# Power_Supply_and_Buttons.net
KiCad netlist of a schematic drawn in Altium Designer
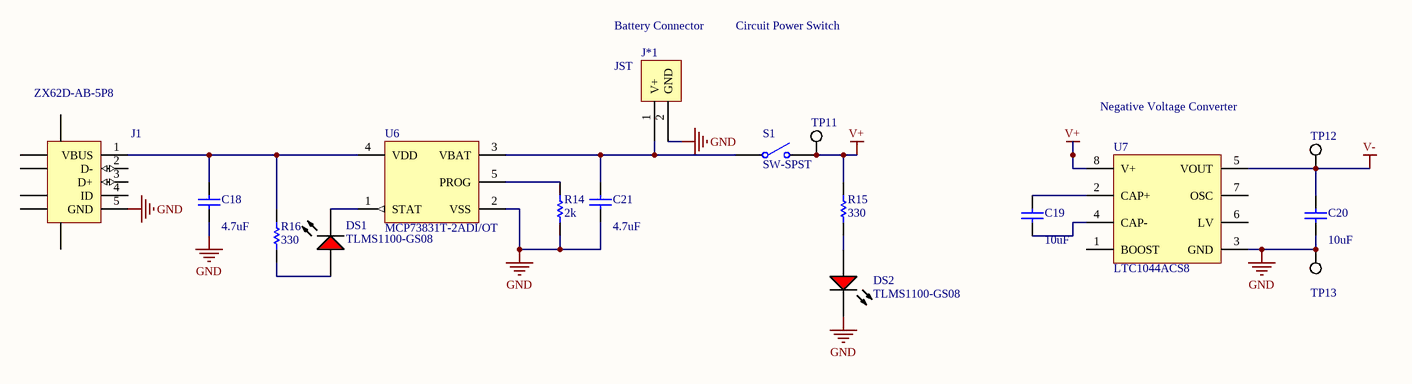
[diagram p0: Power_Supply_and_Buttons.SchDoc]

(export (version "E")
  (design (tool "Eeschema 10.0.6"))
  (components
    (comp (ref "C18")
      (value "4.7uF")
      (footprint "1608[0603]")
      (description "Capacitor (Semiconductor SIM Model)")
      (fields (field (name "PUBLISHER") "Altium Limited"))
      (libsource (lib "Miscellaneous Devices") (part "Cap Semi"))
    )
    (comp (ref "C19")
      (value "10uF")
      (footprint "1608[0603]")
      (description "Capacitor (Semiconductor SIM Model)")
      (fields (field (name "PUBLISHER") "Altium Limited"))
      (libsource (lib "Miscellaneous Devices") (part "Cap Semi"))
    )
    (comp (ref "C20")
      (value "10uF")
      (footprint "1608[0603]")
      (description "Capacitor (Semiconductor SIM Model)")
      (fields (field (name "PUBLISHER") "Altium Limited"))
      (libsource (lib "Miscellaneous Devices") (part "Cap Semi"))
    )
    (comp (ref "C21")
      (value "4.7uF")
      (footprint "1608[0603]")
      (description "Capacitor (Semiconductor SIM Model)")
      (fields (field (name "PUBLISHER") "Altium Limited"))
      (libsource (lib "Miscellaneous Devices") (part "Cap Semi"))
    )
    (comp (ref "DS1")
      (value "TLMS1100-GS08")
      (footprint "VISH-TLMX1100_V")
      (description "LED, RED, 2.1 V, -40 to 100 degC, 2-Pin SMD (0603), RoHS, Tape and Reel")
      (fields (field (name "TOLERANCE") "5%"))
      (libsource (lib "Altium Content Vault") (part "LED-RED-AK-2"))
    )
    (comp (ref "DS2")
      (value "TLMS1100-GS08")
      (footprint "VISH-TLMX1100_V")
      (description "LED, RED, 2.1 V, -40 to 100 degC, 2-Pin SMD (0603), RoHS, Tape and Reel")
      (fields (field (name "TOLERANCE") "5%"))
      (libsource (lib "Altium Content Vault") (part "LED-RED-AK-2"))
    )
    (comp (ref "J*1")
      (value "JST")
      (footprint "JST- S2B-PH-SM4-TB(LF)(SN)-2_V")
      (libsource (lib "JST- S2B-PH-SM4-TB(LF)(SN)-2_V") (part "JST"))
    )
    (comp (ref "J1")
      (value "ZX62D-AB-5P8")
      (footprint "HIRO-ZX62D-AB-5P8_V")
      (fields (field (name "MANUFACTURER") "Hirose Electric"))
      (libsource (lib "Altium Content Vault") (part "HIRO-ZX62D-AB-5P8-5"))
    )
    (comp (ref "R14")
      (value "2k")
      (footprint "6-0805_M")
      (description "Resistor")
      (fields (field (name "PUBLISHER") "Altium Limited"))
      (libsource (lib "Miscellaneous Devices") (part "Res1"))
    )
    (comp (ref "R15")
      (value "330")
      (footprint "6-0805_M")
      (description "Resistor")
      (fields (field (name "PUBLISHER") "Altium Limited"))
      (libsource (lib "Miscellaneous Devices") (part "Res1"))
    )
    (comp (ref "R16")
      (value "330")
      (footprint "6-0805_M")
      (description "Resistor")
      (fields (field (name "PUBLISHER") "Altium Limited"))
      (libsource (lib "Miscellaneous Devices") (part "Res1"))
    )
    (comp (ref "S1")
      (value "SW-SPST")
      (footprint "SPST-2")
      (description "Single-Pole, Single-Throw Switch")
      (fields (field (name "PUBLISHER") "Altium Limited"))
      (libsource (lib "Miscellaneous Devices") (part "SW-SPST"))
    )
    (comp (ref "TP11")
      (value "TESTPOINT_WHITE")
      (footprint "TestPointVia")
      (libsource (lib "altium-import") (part "root_0_TESTPOINT_WHITE_"))
    )
    (comp (ref "TP12")
      (value "TESTPOINT_WHITE")
      (footprint "TestPointVia")
      (libsource (lib "altium-import") (part "root_0_TESTPOINT_WHITE_"))
    )
    (comp (ref "TP13")
      (value "TESTPOINT_WHITE")
      (footprint "TestPointVia")
      (libsource (lib "altium-import") (part "root_2_TESTPOINT_WHITE_"))
    )
    (comp (ref "U6")
      (value "MCP73831T-2ADI/OT")
      (footprint "SOT-23-OT5_M")
      (libsource (lib "Altium Content Vault") (part "PM-BM-MCP73831-SOT5"))
    )
    (comp (ref "U7")
      (value "LTC1044ACS8")
      (footprint "LT-S8-8_M")
      (description "12 V CMOS Voltage Converter, 8-pin SOIC (S8-8), 0 to 70 degC")
      (fields (field (name "MANUFACTURER") "Linear Technology"))
      (libsource (lib "Altium Content Vault") (part "LT-LTC104XX-8"))
    )
  )
  (nets
    (net (code "1") (name "GND") (class "Default")
      (node (ref "C18") (pin "1") (pinfunction "1_1") (pintype "passive"))
      (node (ref "C20") (pin "1") (pinfunction "1_1") (pintype "passive"))
      (node (ref "C21") (pin "1") (pinfunction "1_1") (pintype "passive"))
      (node (ref "DS2") (pin "2") (pinfunction "K_2") (pintype "passive"))
      (node (ref "J*1") (pin "2") (pinfunction "GND_2") (pintype "passive"))
      (node (ref "J1") (pin "5") (pinfunction "GND_5") (pintype "power_in"))
      (node (ref "R14") (pin "1") (pinfunction "1_1") (pintype "passive"))
      (node (ref "TP13") (pin "1") (pinfunction "1_1") (pintype "passive"))
      (node (ref "U6") (pin "2") (pinfunction "VSS_2") (pintype "power_in"))
      (node (ref "U7") (pin "3") (pinfunction "GND_3") (pintype "power_in"))
    )
    (net (code "2") (name "Net-(DS1-A)") (class "Default")
      (node (ref "DS1") (pin "1") (pinfunction "A_1") (pintype "passive"))
      (node (ref "R16") (pin "1") (pinfunction "1_1") (pintype "passive"))
    )
    (net (code "3") (name "Net-(DS1-K)") (class "Default")
      (node (ref "DS1") (pin "2") (pinfunction "K_2") (pintype "passive"))
      (node (ref "U6") (pin "1") (pinfunction "STAT_1") (pintype "output"))
    )
    (net (code "4") (name "Net-(DS2-A)") (class "Default")
      (node (ref "DS2") (pin "1") (pinfunction "A_1") (pintype "passive"))
      (node (ref "R15") (pin "1") (pinfunction "1_1") (pintype "passive"))
    )
    (net (code "5") (name "Net-(J*1-V+)") (class "Default")
      (node (ref "C21") (pin "2") (pinfunction "2_2") (pintype "passive"))
      (node (ref "J*1") (pin "1") (pinfunction "V+_1") (pintype "passive"))
      (node (ref "S1") (pin "1") (pinfunction "COMMON_1") (pintype "passive"))
      (node (ref "U6") (pin "3") (pinfunction "VBAT_3") (pintype "power_in"))
    )
    (net (code "6") (name "Net-(J1-VBUS)") (class "Default")
      (node (ref "C18") (pin "2") (pinfunction "2_2") (pintype "passive"))
      (node (ref "J1") (pin "1") (pinfunction "VBUS_1") (pintype "power_in"))
      (node (ref "R16") (pin "2") (pinfunction "2_2") (pintype "passive"))
      (node (ref "U6") (pin "4") (pinfunction "VDD_4") (pintype "power_in"))
    )
    (net (code "7") (name "Net-(U6-PROG)") (class "Default")
      (node (ref "R14") (pin "2") (pinfunction "2_2") (pintype "passive"))
      (node (ref "U6") (pin "5") (pinfunction "PROG_5") (pintype "passive"))
    )
    (net (code "8") (name "Net-(U7-CAP+)") (class "Default")
      (node (ref "C19") (pin "2") (pinfunction "2_2") (pintype "passive"))
      (node (ref "U7") (pin "2") (pinfunction "CAP+_2") (pintype "passive"))
    )
    (net (code "9") (name "Net-(U7-CAP-)") (class "Default")
      (node (ref "C19") (pin "1") (pinfunction "1_1") (pintype "passive"))
      (node (ref "U7") (pin "4") (pinfunction "CAP-_4") (pintype "passive"))
    )
    (net (code "10") (name "V+") (class "Default")
      (node (ref "R15") (pin "2") (pinfunction "2_2") (pintype "passive"))
      (node (ref "S1") (pin "2") (pinfunction "NO_2") (pintype "passive"))
      (node (ref "TP11") (pin "1") (pinfunction "1_1") (pintype "passive"))
      (node (ref "U7") (pin "8") (pinfunction "V+_8") (pintype "power_in"))
    )
    (net (code "11") (name "V-") (class "Default")
      (node (ref "C20") (pin "2") (pinfunction "2_2") (pintype "passive"))
      (node (ref "TP12") (pin "1") (pinfunction "1_1") (pintype "passive"))
      (node (ref "U7") (pin "5") (pinfunction "VOUT_5") (pintype "power_in"))
    )
    (net (code "12") (name "unconnected-(J1-D+-Pad3)") (class "Default")
      (node (ref "J1") (pin "3") (pinfunction "D+_3") (pintype "bidirectional"))
    )
    (net (code "13") (name "unconnected-(J1-D--Pad2)") (class "Default")
      (node (ref "J1") (pin "2") (pinfunction "D-_2") (pintype "bidirectional"))
    )
    (net (code "14") (name "unconnected-(J1-ID-Pad4)") (class "Default")
      (node (ref "J1") (pin "4") (pinfunction "ID_4") (pintype "passive"))
    )
    (net (code "15") (name "unconnected-(J1-SHLD-Pad6)") (class "Default")
      (node (ref "J1") (pin "6") (pinfunction "SHLD_6") (pintype "passive"))
    )
    (net (code "16") (name "unconnected-(J1-SHLD-Pad7)") (class "Default")
      (node (ref "J1") (pin "7") (pinfunction "SHLD_7") (pintype "passive"))
    )
    (net (code "17") (name "unconnected-(J1-SHLD-Pad8)") (class "Default")
      (node (ref "J1") (pin "8") (pinfunction "SHLD_8") (pintype "passive"))
    )
    (net (code "18") (name "unconnected-(J1-SHLD-Pad9)") (class "Default")
      (node (ref "J1") (pin "9") (pinfunction "SHLD_9") (pintype "passive"))
    )
    (net (code "19") (name "unconnected-(J1-SHLD-Pad10)") (class "Default")
      (node (ref "J1") (pin "10") (pinfunction "SHLD_10") (pintype "passive"))
    )
    (net (code "20") (name "unconnected-(J1-SHLD-Pad11)") (class "Default")
      (node (ref "J1") (pin "11") (pinfunction "SHLD_11") (pintype "passive"))
    )
    (net (code "21") (name "unconnected-(U7-BOOST-Pad1)") (class "Default")
      (node (ref "U7") (pin "1") (pinfunction "BOOST_1") (pintype "passive"))
    )
    (net (code "22") (name "unconnected-(U7-LV-Pad6)") (class "Default")
      (node (ref "U7") (pin "6") (pinfunction "LV_6") (pintype "passive"))
    )
    (net (code "23") (name "unconnected-(U7-OSC-Pad7)") (class "Default")
      (node (ref "U7") (pin "7") (pinfunction "OSC_7") (pintype "passive"))
    )
  )
)
